# Compressor.net
KiCad netlist of a schematic drawn in EAGLE
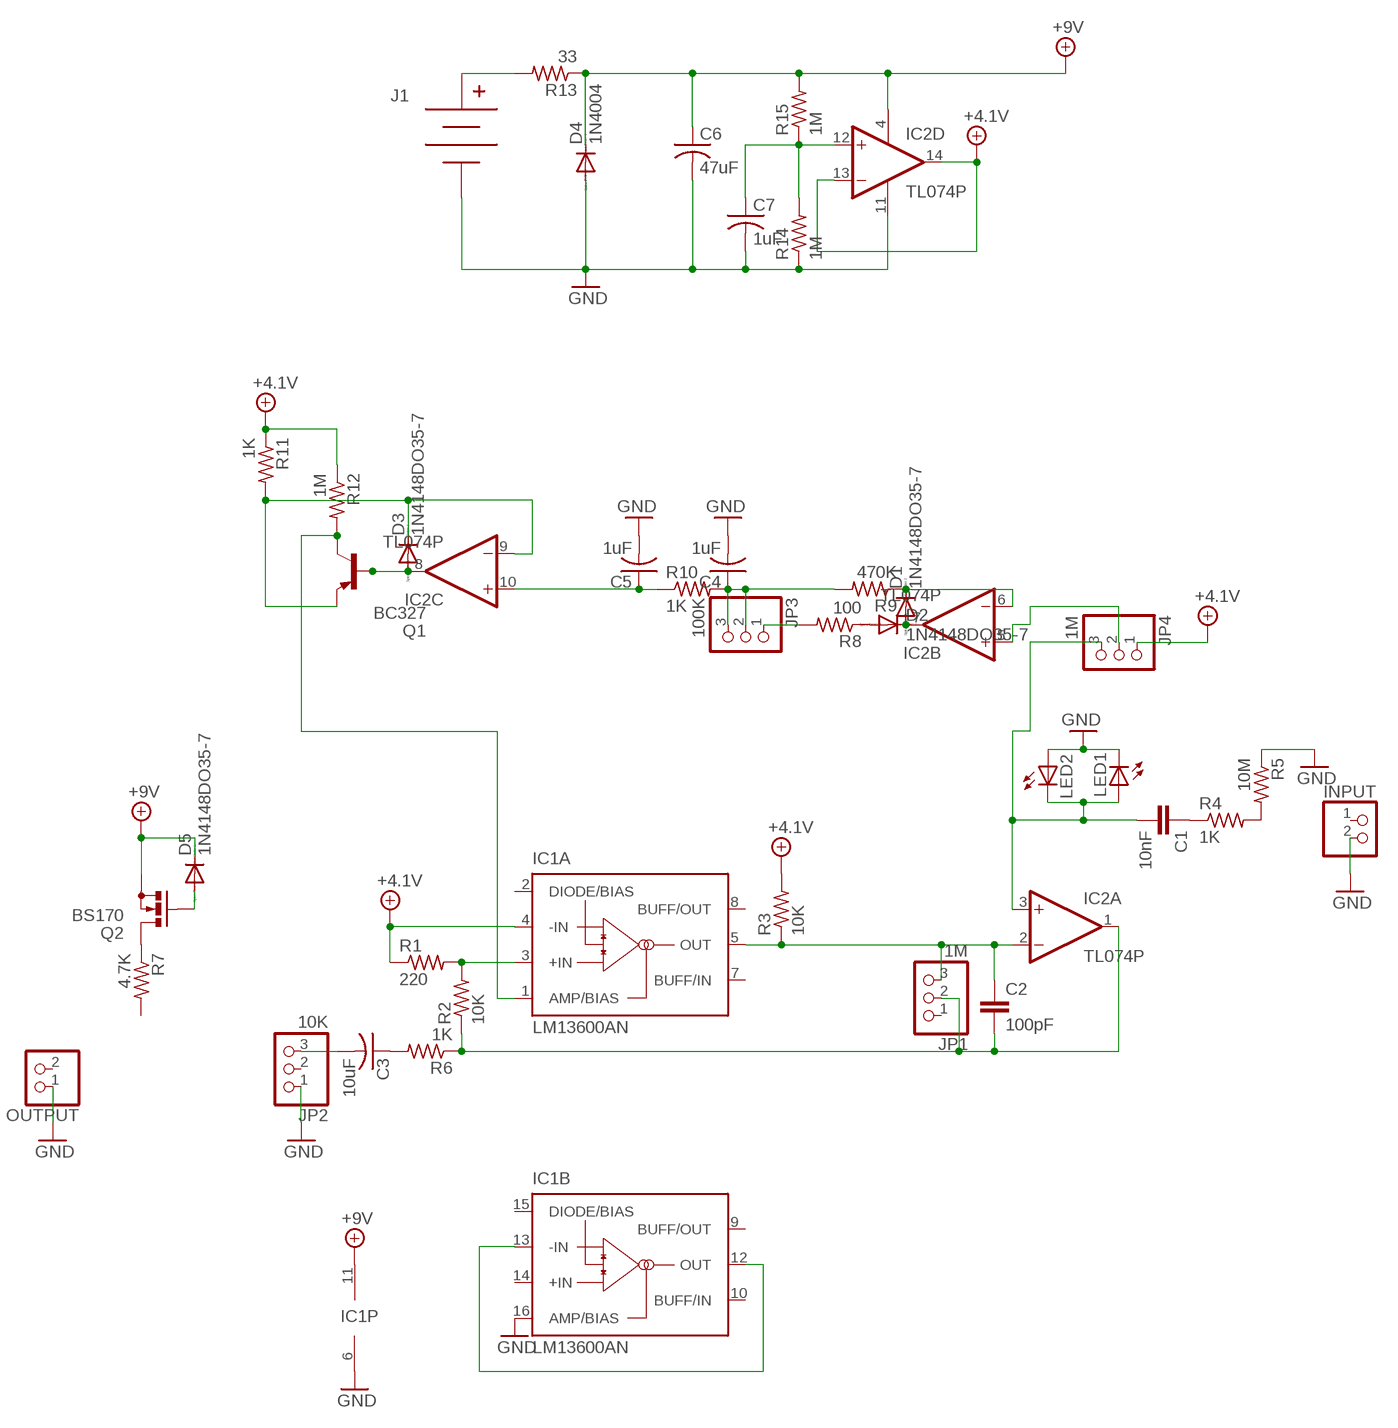
[diagram p0: schematic, sheet 1]

(export (version "E")
  (design (tool "Eeschema 10.0.6"))
  (components
    (comp (ref "C1")
      (value "10nF")
      (footprint "eagle-import:C025-030X050")
      (libsource (lib "eagle-import") (part "C-EU025-030X050"))
    )
    (comp (ref "C2")
      (value "100pF")
      (footprint "eagle-import:C025-030X050")
      (libsource (lib "eagle-import") (part "C-EU025-030X050"))
    )
    (comp (ref "C3")
      (value "10uF")
      (footprint "eagle-import:C025-040X050")
      (libsource (lib "eagle-import") (part "C-US025-040X050"))
    )
    (comp (ref "C4")
      (value "1uF")
      (footprint "eagle-import:C025-040X050")
      (libsource (lib "eagle-import") (part "C-US025-040X050"))
    )
    (comp (ref "C5")
      (value "1uF")
      (footprint "eagle-import:C025-040X050")
      (libsource (lib "eagle-import") (part "C-US025-040X050"))
    )
    (comp (ref "C6")
      (value "47uF")
      (footprint "eagle-import:C025-040X050")
      (libsource (lib "eagle-import") (part "C-US025-040X050"))
    )
    (comp (ref "C7")
      (value "1uF")
      (footprint "eagle-import:C025-040X050")
      (libsource (lib "eagle-import") (part "C-US025-040X050"))
    )
    (comp (ref "D1")
      (value "1N4148DO35-7")
      (footprint "eagle-import:DO35-7")
      (libsource (lib "eagle-import") (part "1N4148DO35-7"))
    )
    (comp (ref "D2")
      (value "1N4148DO35-7")
      (footprint "eagle-import:DO35-7")
      (libsource (lib "eagle-import") (part "1N4148DO35-7"))
    )
    (comp (ref "D3")
      (value "1N4148DO35-7")
      (footprint "eagle-import:DO35-7")
      (libsource (lib "eagle-import") (part "1N4148DO35-7"))
    )
    (comp (ref "D4")
      (value "1N4004")
      (footprint "eagle-import:DO41-10")
      (libsource (lib "eagle-import") (part "1N4004"))
    )
    (comp (ref "D5")
      (value "1N4148DO35-7")
      (footprint "eagle-import:DO35-7")
      (libsource (lib "eagle-import") (part "1N4148DO35-7"))
    )
    (comp (ref "IC1")
      (value "LM13600AN")
      (footprint "eagle-import:DIL16")
      (libsource (lib "eagle-import") (part "LM13600NA"))
    )
    (comp (ref "IC2")
      (value "TL074P")
      (footprint "eagle-import:DIL14")
      (libsource (lib "eagle-import") (part "TL074P"))
    )
    (comp (ref "INPUT")
      (value "PINHD-1X2")
      (footprint "eagle-import:1X02")
      (libsource (lib "eagle-import") (part "PINHD-1X2"))
    )
    (comp (ref "J1")
      (value "BC9VPC")
      (footprint "eagle-import:BC9VPC")
      (libsource (lib "eagle-import") (part "BC9VPC"))
    )
    (comp (ref "JP1")
      (value "1M")
      (footprint "eagle-import:1X03")
      (libsource (lib "eagle-import") (part "PINHD-1X3"))
    )
    (comp (ref "JP2")
      (value "10K")
      (footprint "eagle-import:1X03")
      (libsource (lib "eagle-import") (part "PINHD-1X3"))
    )
    (comp (ref "JP3")
      (value "100K")
      (footprint "eagle-import:1X03")
      (libsource (lib "eagle-import") (part "PINHD-1X3"))
    )
    (comp (ref "JP4")
      (value "1M")
      (footprint "eagle-import:1X03")
      (libsource (lib "eagle-import") (part "PINHD-1X3"))
    )
    (comp (ref "LED1")
      (value "LEDLZR181")
      (footprint "eagle-import:LZR181")
      (libsource (lib "eagle-import") (part "LEDLZR181"))
    )
    (comp (ref "LED2")
      (value "LEDLZR181")
      (footprint "eagle-import:LZR181")
      (libsource (lib "eagle-import") (part "LEDLZR181"))
    )
    (comp (ref "OUTPUT")
      (value "PINHD-1X2")
      (footprint "eagle-import:1X02")
      (libsource (lib "eagle-import") (part "PINHD-1X2"))
    )
    (comp (ref "Q1")
      (value "BC327")
      (footprint "eagle-import:TO92")
      (libsource (lib "eagle-import") (part "BC327"))
    )
    (comp (ref "Q2")
      (value "BS170")
      (footprint "eagle-import:SOT54E")
      (libsource (lib "eagle-import") (part "BS170"))
    )
    (comp (ref "R1")
      (value "220")
      (footprint "eagle-import:0207_7")
      (libsource (lib "eagle-import") (part "R-US_0207/7"))
    )
    (comp (ref "R2")
      (value "10K")
      (footprint "eagle-import:0207_7")
      (libsource (lib "eagle-import") (part "R-US_0207/7"))
    )
    (comp (ref "R3")
      (value "10K")
      (footprint "eagle-import:0207_7")
      (libsource (lib "eagle-import") (part "R-US_0207/7"))
    )
    (comp (ref "R4")
      (value "1K")
      (footprint "eagle-import:0207_7")
      (libsource (lib "eagle-import") (part "R-US_0207/7"))
    )
    (comp (ref "R5")
      (value "10M")
      (footprint "eagle-import:0207_7")
      (libsource (lib "eagle-import") (part "R-US_0207/7"))
    )
    (comp (ref "R6")
      (value "1K")
      (footprint "eagle-import:0207_7")
      (libsource (lib "eagle-import") (part "R-US_0207/7"))
    )
    (comp (ref "R7")
      (value "4.7K")
      (footprint "eagle-import:0207_7")
      (libsource (lib "eagle-import") (part "R-US_0207/7"))
    )
    (comp (ref "R8")
      (value "100")
      (footprint "eagle-import:0207_7")
      (libsource (lib "eagle-import") (part "R-US_0207/7"))
    )
    (comp (ref "R9")
      (value "470K")
      (footprint "eagle-import:0207_7")
      (libsource (lib "eagle-import") (part "R-US_0207/7"))
    )
    (comp (ref "R10")
      (value "1K")
      (footprint "eagle-import:0207_7")
      (libsource (lib "eagle-import") (part "R-US_0207/7"))
    )
    (comp (ref "R11")
      (value "1K")
      (footprint "eagle-import:0207_7")
      (libsource (lib "eagle-import") (part "R-US_0207/7"))
    )
    (comp (ref "R12")
      (value "1M")
      (footprint "eagle-import:0207_7")
      (libsource (lib "eagle-import") (part "R-US_0207/7"))
    )
    (comp (ref "R13")
      (value "33")
      (footprint "eagle-import:0207_7")
      (libsource (lib "eagle-import") (part "R-US_0207/7"))
    )
    (comp (ref "R14")
      (value "1M")
      (footprint "eagle-import:0207_7")
      (libsource (lib "eagle-import") (part "R-US_0207/7"))
    )
    (comp (ref "R15")
      (value "1M")
      (footprint "eagle-import:0207_7")
      (libsource (lib "eagle-import") (part "R-US_0207/7"))
    )
  )
  (nets
    (net (code "1") (name "+4.1V") (class "Default")
      (node (ref "IC1") (pin "4") (pinfunction "-IN_4") (pintype "input"))
      (node (ref "IC2") (pin "13") (pinfunction "-IN_13") (pintype "input"))
      (node (ref "IC2") (pin "14") (pinfunction "OUT_14") (pintype "output"))
      (node (ref "JP4") (pin "1") (pinfunction "1_1") (pintype "passive"))
      (node (ref "R1") (pin "1") (pinfunction "1_1") (pintype "passive"))
      (node (ref "R11") (pin "1") (pinfunction "1_1") (pintype "passive"))
      (node (ref "R12") (pin "1") (pinfunction "1_1") (pintype "passive"))
      (node (ref "R3") (pin "2") (pinfunction "2_2") (pintype "passive"))
    )
    (net (code "2") (name "+9V") (class "Default")
      (node (ref "C6") (pin "1") (pinfunction "1_1") (pintype "passive"))
      (node (ref "D4") (pin "C") (pinfunction "C_C") (pintype "passive"))
      (node (ref "D5") (pin "C") (pinfunction "C_C") (pintype "passive"))
      (node (ref "IC1") (pin "11") (pinfunction "V+_11") (pintype "power_in"))
      (node (ref "IC2") (pin "4") (pinfunction "V+_4") (pintype "power_in"))
      (node (ref "Q2") (pin "S") (pinfunction "S_S") (pintype "passive"))
      (node (ref "R13") (pin "1") (pinfunction "1_1") (pintype "passive"))
      (node (ref "R15") (pin "2") (pinfunction "2_2") (pintype "passive"))
    )
    (net (code "3") (name "GND") (class "Default")
      (node (ref "C4") (pin "2") (pinfunction "2_2") (pintype "passive"))
      (node (ref "C5") (pin "2") (pinfunction "2_2") (pintype "passive"))
      (node (ref "C6") (pin "2") (pinfunction "2_2") (pintype "passive"))
      (node (ref "C7") (pin "2") (pinfunction "2_2") (pintype "passive"))
      (node (ref "D4") (pin "A") (pinfunction "A_A") (pintype "passive"))
      (node (ref "IC1") (pin "16") (pinfunction "AMP/BIAS_16") (pintype "passive"))
      (node (ref "IC1") (pin "6") (pinfunction "V-_6") (pintype "power_in"))
      (node (ref "IC2") (pin "11") (pinfunction "V-_11") (pintype "power_in"))
      (node (ref "INPUT") (pin "2") (pinfunction "2_2") (pintype "passive"))
      (node (ref "J1") (pin "V-") (pinfunction "V-_V-") (pintype "bidirectional"))
      (node (ref "JP2") (pin "1") (pinfunction "1_1") (pintype "passive"))
      (node (ref "LED1") (pin "K") (pinfunction "C_K") (pintype "passive"))
      (node (ref "LED2") (pin "A") (pinfunction "A_A") (pintype "passive"))
      (node (ref "OUTPUT") (pin "1") (pinfunction "1_1") (pintype "passive"))
      (node (ref "R14") (pin "1") (pinfunction "1_1") (pintype "passive"))
      (node (ref "R5") (pin "1") (pinfunction "1_1") (pintype "passive"))
    )
    (net (code "4") (name "Net-(C1-Pad1)") (class "Default")
      (node (ref "C1") (pin "1") (pinfunction "1_1") (pintype "passive"))
      (node (ref "R4") (pin "1") (pinfunction "1_1") (pintype "passive"))
    )
    (net (code "5") (name "Net-(C3-Pad1)") (class "Default")
      (node (ref "C3") (pin "1") (pinfunction "1_1") (pintype "passive"))
      (node (ref "R6") (pin "2") (pinfunction "2_2") (pintype "passive"))
    )
    (net (code "6") (name "Net-(C3-Pad2)") (class "Default")
      (node (ref "C3") (pin "2") (pinfunction "2_2") (pintype "passive"))
      (node (ref "JP2") (pin "3") (pinfunction "3_3") (pintype "passive"))
    )
    (net (code "7") (name "Net-(C4-Pad1)") (class "Default")
      (node (ref "C4") (pin "1") (pinfunction "1_1") (pintype "passive"))
      (node (ref "JP3") (pin "2") (pinfunction "2_2") (pintype "passive"))
      (node (ref "JP3") (pin "3") (pinfunction "3_3") (pintype "passive"))
      (node (ref "R10") (pin "2") (pinfunction "2_2") (pintype "passive"))
      (node (ref "R9") (pin "2") (pinfunction "2_2") (pintype "passive"))
    )
    (net (code "8") (name "Net-(D2-PadA)") (class "Default")
      (node (ref "D2") (pin "A") (pinfunction "A_A") (pintype "passive"))
      (node (ref "R8") (pin "1") (pinfunction "1_1") (pintype "passive"))
    )
    (net (code "9") (name "Net-(D5-PadA)") (class "Default")
      (node (ref "D5") (pin "A") (pinfunction "A_A") (pintype "passive"))
      (node (ref "Q2") (pin "G") (pinfunction "G_G") (pintype "passive"))
    )
    (net (code "10") (name "Net-(IC1A-+IN)") (class "Default")
      (node (ref "IC1") (pin "3") (pinfunction "+IN_3") (pintype "input"))
      (node (ref "R1") (pin "2") (pinfunction "2_2") (pintype "passive"))
      (node (ref "R2") (pin "2") (pinfunction "2_2") (pintype "passive"))
    )
    (net (code "11") (name "Net-(IC1A-AMP{slash}BIAS)") (class "Default")
      (node (ref "IC1") (pin "1") (pinfunction "AMP/BIAS_1") (pintype "passive"))
      (node (ref "Q1") (pin "3") (pinfunction "C_3") (pintype "passive"))
      (node (ref "R12") (pin "2") (pinfunction "2_2") (pintype "passive"))
    )
    (net (code "12") (name "Net-(IC1A-OUT)") (class "Default")
      (node (ref "C2") (pin "1") (pinfunction "1_1") (pintype "passive"))
      (node (ref "IC1") (pin "5") (pinfunction "OUT_5") (pintype "output"))
      (node (ref "IC2") (pin "2") (pinfunction "-IN_2") (pintype "input"))
      (node (ref "JP1") (pin "3") (pinfunction "3_3") (pintype "passive"))
      (node (ref "R3") (pin "1") (pinfunction "1_1") (pintype "passive"))
    )
    (net (code "13") (name "Net-(IC1B--IN)") (class "Default")
      (node (ref "IC1") (pin "12") (pinfunction "OUT_12") (pintype "output"))
      (node (ref "IC1") (pin "13") (pinfunction "-IN_13") (pintype "input"))
    )
    (net (code "14") (name "Net-(IC2A-+IN)") (class "Default")
      (node (ref "C1") (pin "2") (pinfunction "2_2") (pintype "passive"))
      (node (ref "IC2") (pin "3") (pinfunction "+IN_3") (pintype "input"))
      (node (ref "JP4") (pin "3") (pinfunction "3_3") (pintype "passive"))
      (node (ref "LED1") (pin "A") (pinfunction "A_A") (pintype "passive"))
      (node (ref "LED2") (pin "K") (pinfunction "C_K") (pintype "passive"))
    )
    (net (code "15") (name "Net-(IC2A-OUT)") (class "Default")
      (node (ref "C2") (pin "2") (pinfunction "2_2") (pintype "passive"))
      (node (ref "IC2") (pin "1") (pinfunction "OUT_1") (pintype "output"))
      (node (ref "JP1") (pin "2") (pinfunction "2_2") (pintype "passive"))
      (node (ref "R2") (pin "1") (pinfunction "1_1") (pintype "passive"))
      (node (ref "R6") (pin "1") (pinfunction "1_1") (pintype "passive"))
    )
    (net (code "16") (name "Net-(IC2B-+IN)") (class "Default")
      (node (ref "IC2") (pin "5") (pinfunction "+IN_5") (pintype "input"))
      (node (ref "JP4") (pin "2") (pinfunction "2_2") (pintype "passive"))
    )
    (net (code "17") (name "Net-(IC2B--IN)") (class "Default")
      (node (ref "D1") (pin "C") (pinfunction "C_C") (pintype "passive"))
      (node (ref "IC2") (pin "6") (pinfunction "-IN_6") (pintype "input"))
      (node (ref "R9") (pin "1") (pinfunction "1_1") (pintype "passive"))
    )
    (net (code "18") (name "Net-(IC2B-OUT)") (class "Default")
      (node (ref "D1") (pin "A") (pinfunction "A_A") (pintype "passive"))
      (node (ref "D2") (pin "C") (pinfunction "C_C") (pintype "passive"))
      (node (ref "IC2") (pin "7") (pinfunction "OUT_7") (pintype "output"))
    )
    (net (code "19") (name "Net-(IC2C-+IN)") (class "Default")
      (node (ref "C5") (pin "1") (pinfunction "1_1") (pintype "passive"))
      (node (ref "IC2") (pin "10") (pinfunction "+IN_10") (pintype "input"))
      (node (ref "R10") (pin "1") (pinfunction "1_1") (pintype "passive"))
    )
    (net (code "20") (name "Net-(IC2C--IN)") (class "Default")
      (node (ref "D3") (pin "C") (pinfunction "C_C") (pintype "passive"))
      (node (ref "IC2") (pin "9") (pinfunction "-IN_9") (pintype "input"))
      (node (ref "Q1") (pin "1") (pinfunction "E_1") (pintype "passive"))
      (node (ref "R11") (pin "2") (pinfunction "2_2") (pintype "passive"))
    )
    (net (code "21") (name "Net-(IC2C-OUT)") (class "Default")
      (node (ref "D3") (pin "A") (pinfunction "A_A") (pintype "passive"))
      (node (ref "IC2") (pin "8") (pinfunction "OUT_8") (pintype "output"))
      (node (ref "Q1") (pin "2") (pinfunction "B_2") (pintype "passive"))
    )
    (net (code "22") (name "Net-(IC2D-+IN)") (class "Default")
      (node (ref "C7") (pin "1") (pinfunction "1_1") (pintype "passive"))
      (node (ref "IC2") (pin "12") (pinfunction "+IN_12") (pintype "input"))
      (node (ref "R14") (pin "2") (pinfunction "2_2") (pintype "passive"))
      (node (ref "R15") (pin "1") (pinfunction "1_1") (pintype "passive"))
    )
    (net (code "23") (name "Net-(J1-PadV+)") (class "Default")
      (node (ref "J1") (pin "V+") (pinfunction "V+_V+") (pintype "bidirectional"))
      (node (ref "R13") (pin "2") (pinfunction "2_2") (pintype "passive"))
    )
    (net (code "24") (name "Net-(JP3-Pad1)") (class "Default")
      (node (ref "JP3") (pin "1") (pinfunction "1_1") (pintype "passive"))
      (node (ref "R8") (pin "2") (pinfunction "2_2") (pintype "passive"))
    )
    (net (code "25") (name "Net-(Q2-PadD)") (class "Default")
      (node (ref "Q2") (pin "D") (pinfunction "D_D") (pintype "passive"))
      (node (ref "R7") (pin "1") (pinfunction "1_1") (pintype "passive"))
    )
    (net (code "26") (name "Net-(R4-Pad2)") (class "Default")
      (node (ref "R4") (pin "2") (pinfunction "2_2") (pintype "passive"))
      (node (ref "R5") (pin "2") (pinfunction "2_2") (pintype "passive"))
    )
    (net (code "27") (name "unconnected-(IC1A-BUFF{slash}IN-Pad7)") (class "Default")
      (node (ref "IC1") (pin "7") (pinfunction "BUFF/IN_7") (pintype "input"))
    )
    (net (code "28") (name "unconnected-(IC1A-BUFF{slash}OUT-Pad8)") (class "Default")
      (node (ref "IC1") (pin "8") (pinfunction "BUFF/OUT_8") (pintype "output"))
    )
    (net (code "29") (name "unconnected-(IC1A-DIODE{slash}BIAS-Pad2)") (class "Default")
      (node (ref "IC1") (pin "2") (pinfunction "DIODE/BIAS_2") (pintype "passive"))
    )
    (net (code "30") (name "unconnected-(IC1B-+IN-Pad14)") (class "Default")
      (node (ref "IC1") (pin "14") (pinfunction "+IN_14") (pintype "input"))
    )
    (net (code "31") (name "unconnected-(IC1B-BUFF{slash}IN-Pad10)") (class "Default")
      (node (ref "IC1") (pin "10") (pinfunction "BUFF/IN_10") (pintype "input"))
    )
    (net (code "32") (name "unconnected-(IC1B-BUFF{slash}OUT-Pad9)") (class "Default")
      (node (ref "IC1") (pin "9") (pinfunction "BUFF/OUT_9") (pintype "output"))
    )
    (net (code "33") (name "unconnected-(IC1B-DIODE{slash}BIAS-Pad15)") (class "Default")
      (node (ref "IC1") (pin "15") (pinfunction "DIODE/BIAS_15") (pintype "passive"))
    )
    (net (code "34") (name "unconnected-(INPUT-Pad1)") (class "Default")
      (node (ref "INPUT") (pin "1") (pinfunction "1_1") (pintype "passive"))
    )
    (net (code "35") (name "unconnected-(JP1-Pad1)") (class "Default")
      (node (ref "JP1") (pin "1") (pinfunction "1_1") (pintype "passive"))
    )
    (net (code "36") (name "unconnected-(JP2-Pad2)") (class "Default")
      (node (ref "JP2") (pin "2") (pinfunction "2_2") (pintype "passive"))
    )
    (net (code "37") (name "unconnected-(OUTPUT-Pad2)") (class "Default")
      (node (ref "OUTPUT") (pin "2") (pinfunction "2_2") (pintype "passive"))
    )
    (net (code "38") (name "unconnected-(R7-Pad2)") (class "Default")
      (node (ref "R7") (pin "2") (pinfunction "2_2") (pintype "passive"))
    )
  )
)
